# ethernet.net
KiCad netlist of a schematic drawn in Altium Designer
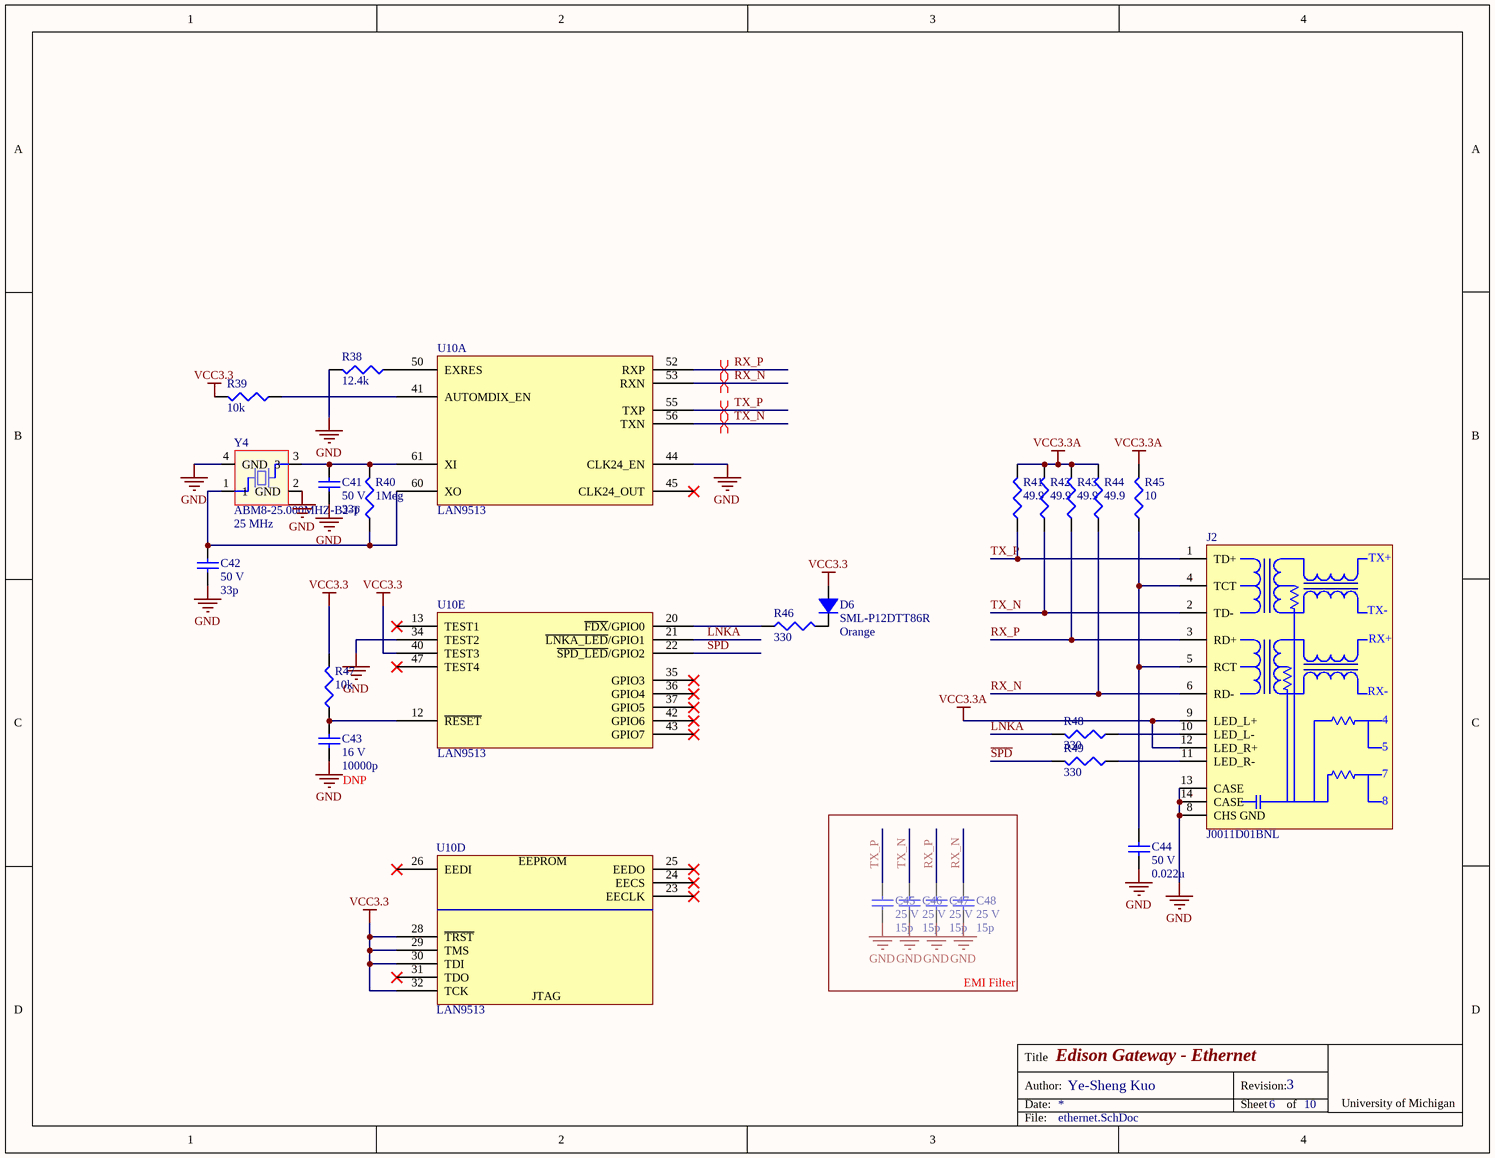
[diagram p0: ethernet.SchDoc]

(export (version "E")
  (design (tool "Eeschema 10.0.6"))
  (components
    (comp (ref "C41")
      (value "33p")
      (footprint "0402")
      (description "33pF ±5% 50V Ceramic Capacitor C0G, NP0 0402")
      (fields
        (field (name "VOLTAGE RATED") "50 V")
        (field (name "TOLERANCE") "5%")
        (field (name "MANUFACTURER PART NUMBER") "GRM1555C1H330JA01D")
      )
      (libsource (lib "capacitors") (part "GRM1555C1H330JA01D"))
    )
    (comp (ref "C42")
      (value "33p")
      (footprint "0402")
      (description "33pF ±5% 50V Ceramic Capacitor C0G, NP0 0402")
      (fields
        (field (name "VOLTAGE RATED") "50 V")
        (field (name "TOLERANCE") "5%")
        (field (name "MANUFACTURER PART NUMBER") "GRM1555C1H330JA01D")
      )
      (libsource (lib "capacitors") (part "GRM1555C1H330JA01D"))
    )
    (comp (ref "C43")
      (value "10000p")
      (footprint "0402")
      (description "10000pF ±10% 16V Ceramic Capacitor X7R 0402")
      (fields
        (field (name "TOLERANCE") "10%")
        (field (name "VOLTAGE RATED") "16 V")
        (field (name "MANUFACTURER PART NUMBER") "GRM155R71C103KA01D")
        (field (name "NOTE") "DNP")
      )
      (libsource (lib "capacitors") (part "GRM155R71C103KA01D"))
    )
    (comp (ref "C44")
      (value "0.022u")
      (footprint "0402")
      (description "0.022µF ±10% 50V Ceramic Capacitor X7R 0402")
      (fields
        (field (name "TOLERANCE") "10%")
        (field (name "VOLTAGE RATED") "50 V")
        (field (name "MANUFACTURER PART NUMBER") "GRM155R71H223KA12D")
      )
      (libsource (lib "capacitors") (part "GRM155R71H223KA12D"))
    )
    (comp (ref "C45")
      (value "15p")
      (footprint "0402")
      (description "15pF ±5% 25V Ceramic Capacitor C0G, NP0 0402")
      (fields
        (field (name "VOLTAGE RATED") "25 V")
        (field (name "TOLERANCE") "5%")
        (field (name "MANUFACTURER PART NUMBER") "GRM1555C1E150JA01D")
      )
      (libsource (lib "capacitors") (part "GRM1555C1E150JA01D"))
    )
    (comp (ref "C46")
      (value "15p")
      (footprint "0402")
      (description "15pF ±5% 25V Ceramic Capacitor C0G, NP0 0402")
      (fields
        (field (name "VOLTAGE RATED") "25 V")
        (field (name "TOLERANCE") "5%")
        (field (name "MANUFACTURER PART NUMBER") "GRM1555C1E150JA01D")
      )
      (libsource (lib "capacitors") (part "GRM1555C1E150JA01D"))
    )
    (comp (ref "C47")
      (value "15p")
      (footprint "0402")
      (description "15pF ±5% 25V Ceramic Capacitor C0G, NP0 0402")
      (fields
        (field (name "VOLTAGE RATED") "25 V")
        (field (name "TOLERANCE") "5%")
        (field (name "MANUFACTURER PART NUMBER") "GRM1555C1E150JA01D")
      )
      (libsource (lib "capacitors") (part "GRM1555C1E150JA01D"))
    )
    (comp (ref "C48")
      (value "15p")
      (footprint "0402")
      (description "15pF ±5% 25V Ceramic Capacitor C0G, NP0 0402")
      (fields
        (field (name "VOLTAGE RATED") "25 V")
        (field (name "TOLERANCE") "5%")
        (field (name "MANUFACTURER PART NUMBER") "GRM1555C1E150JA01D")
      )
      (libsource (lib "capacitors") (part "GRM1555C1E150JA01D"))
    )
    (comp (ref "D6")
      (value "SML-P12DTT86R")
      (footprint "0402 - LED")
      (description "Orange 605nm LED Indication - Discrete 2.1V 0402")
      (fields (field (name "MANUFACTURER") "Rohm Semiconductor") (field (name "ALTIUM_VALUE") "Orange"))
      (libsource (lib "LED") (part "SML-P12DTT86R"))
    )
    (comp (ref "J2")
      (value "J0011D01BNL")
      (footprint "J0011D01BNL")
      (description "1x1 Tab-Down RJ45")
      (libsource (lib "connectors") (part "J0011D01BNL"))
    )
    (comp (ref "R38")
      (value "12.4k")
      (footprint "0402")
      (description "RES SMD 12.4K OHM 1% 1/16W 0402")
      (fields (field (name "TOLERANCE") "1%") (field (name "POWER") "1/16 W"))
      (libsource (lib "resistors") (part "RC0402FR-0712K4L"))
    )
    (comp (ref "R39")
      (value "10k")
      (footprint "0402")
      (description "RES SMD 10K OHM 1% 1/16W 0402")
      (fields (field (name "TOLERANCE") "1%") (field (name "POWER") "1/16 W"))
      (libsource (lib "resistors") (part "CRCW040210K0FKED"))
    )
    (comp (ref "R40")
      (value "1Meg")
      (footprint "0402")
      (description "RES SMD 1M OHM 1% 1/16W 0402")
      (fields (field (name "TOLERANCE") "1%") (field (name "POWER") "1/16 W"))
      (libsource (lib "resistors") (part "CRCW04021M00FKED"))
    )
    (comp (ref "R41")
      (value "49.9")
      (footprint "0402")
      (description "RES SMD 49.9 OHM 1% 1/16W 0402")
      (fields (field (name "TOLERANCE") "1%") (field (name "POWER") "1/16 W"))
      (libsource (lib "resistors") (part "CRCW040249R9FKED"))
    )
    (comp (ref "R42")
      (value "49.9")
      (footprint "0402")
      (description "RES SMD 49.9 OHM 1% 1/16W 0402")
      (fields (field (name "TOLERANCE") "1%") (field (name "POWER") "1/16 W"))
      (libsource (lib "resistors") (part "CRCW040249R9FKED"))
    )
    (comp (ref "R43")
      (value "49.9")
      (footprint "0402")
      (description "RES SMD 49.9 OHM 1% 1/16W 0402")
      (fields (field (name "TOLERANCE") "1%") (field (name "POWER") "1/16 W"))
      (libsource (lib "resistors") (part "CRCW040249R9FKED"))
    )
    (comp (ref "R44")
      (value "49.9")
      (footprint "0402")
      (description "RES SMD 49.9 OHM 1% 1/16W 0402")
      (fields (field (name "TOLERANCE") "1%") (field (name "POWER") "1/16 W"))
      (libsource (lib "resistors") (part "CRCW040249R9FKED"))
    )
    (comp (ref "R45")
      (value "10")
      (footprint "0402")
      (description "RES SMD 10 OHM 1% 1/16W 0402")
      (fields (field (name "TOLERANCE") "1%") (field (name "POWER") "1/16 W"))
      (libsource (lib "resistors") (part "CRCW040210R0FKED"))
    )
    (comp (ref "R46")
      (value "330")
      (footprint "0402")
      (description "RES SMD 330 OHM 1% 1/16W 0402")
      (fields (field (name "TOLERANCE") "1%") (field (name "POWER") "1/16 W"))
      (libsource (lib "resistors") (part "CRCW0402330RFKED"))
    )
    (comp (ref "R47")
      (value "10k")
      (footprint "0402")
      (description "RES SMD 10K OHM 1% 1/16W 0402")
      (fields (field (name "TOLERANCE") "1%") (field (name "POWER") "1/16 W"))
      (libsource (lib "resistors") (part "CRCW040210K0FKED"))
    )
    (comp (ref "R48")
      (value "330")
      (footprint "0402")
      (description "RES SMD 330 OHM 1% 1/16W 0402")
      (fields (field (name "TOLERANCE") "1%") (field (name "POWER") "1/16 W"))
      (libsource (lib "resistors") (part "CRCW0402330RFKED"))
    )
    (comp (ref "R49")
      (value "330")
      (footprint "0402")
      (description "RES SMD 330 OHM 1% 1/16W 0402")
      (fields (field (name "TOLERANCE") "1%") (field (name "POWER") "1/16 W"))
      (libsource (lib "resistors") (part "CRCW0402330RFKED"))
    )
    (comp (ref "U10")
      (value "LAN9513")
      (footprint "QFN-64")
      (description "USB 2.0 Hub and 10/100  Ethernet Controller")
      (libsource (lib "ethernet controller") (part "LAN9513"))
    )
    (comp (ref "Y4")
      (value "ABM8-25.000MHZ-B2-T")
      (footprint "ABM8")
      (description "Crystal 25.0000MHz 20ppm 18pF 50 Ohm")
      (fields (field (name "FREQUENCY") "25 MHz"))
      (libsource (lib "crystal oscillators") (part "ABM8-25.000MHZ-B2-T"))
    )
  )
  (nets
    (net (code "1") (name "/RX_N") (class "Default")
      (node (ref "C48") (pin "1") (pintype "passive"))
      (node (ref "J2") (pin "6") (pinfunction "RD-_6") (pintype "passive"))
      (node (ref "R44") (pin "2") (pintype "passive"))
      (node (ref "U10") (pin "53") (pinfunction "RXN_53") (pintype "passive"))
    )
    (net (code "2") (name "/RX_P") (class "Default")
      (node (ref "C47") (pin "1") (pintype "passive"))
      (node (ref "J2") (pin "3") (pinfunction "RD+_3") (pintype "passive"))
      (node (ref "R43") (pin "2") (pintype "passive"))
      (node (ref "U10") (pin "52") (pinfunction "RXP_52") (pintype "passive"))
    )
    (net (code "3") (name "/TX_N") (class "Default")
      (node (ref "C46") (pin "1") (pintype "passive"))
      (node (ref "J2") (pin "2") (pinfunction "TD-_2") (pintype "passive"))
      (node (ref "R42") (pin "2") (pintype "passive"))
      (node (ref "U10") (pin "56") (pinfunction "TXN_56") (pintype "passive"))
    )
    (net (code "4") (name "/TX_P") (class "Default")
      (node (ref "C45") (pin "1") (pintype "passive"))
      (node (ref "J2") (pin "1") (pinfunction "TD+_1") (pintype "passive"))
      (node (ref "R41") (pin "2") (pintype "passive"))
      (node (ref "U10") (pin "55") (pinfunction "TXP_55") (pintype "passive"))
    )
    (net (code "5") (name "/~{LNKA}") (class "Default")
      (node (ref "R48") (pin "1") (pintype "passive"))
      (node (ref "U10") (pin "21") (pinfunction "~{LNKA_LED}/GPIO1_21") (pintype "passive"))
    )
    (net (code "6") (name "/~{SPD}") (class "Default")
      (node (ref "R49") (pin "1") (pintype "passive"))
      (node (ref "U10") (pin "22") (pinfunction "~{SPD_LED}/GPIO2_22") (pintype "passive"))
    )
    (net (code "7") (name "GND") (class "Default")
      (node (ref "C41") (pin "2") (pintype "passive"))
      (node (ref "C42") (pin "2") (pintype "passive"))
      (node (ref "C43") (pin "2") (pintype "passive"))
      (node (ref "C44") (pin "2") (pintype "passive"))
      (node (ref "C45") (pin "2") (pintype "passive"))
      (node (ref "C46") (pin "2") (pintype "passive"))
      (node (ref "C47") (pin "2") (pintype "passive"))
      (node (ref "C48") (pin "2") (pintype "passive"))
      (node (ref "J2") (pin "13") (pinfunction "CASE_13") (pintype "passive"))
      (node (ref "J2") (pin "14") (pinfunction "CASE_14") (pintype "passive"))
      (node (ref "J2") (pin "8") (pinfunction "CHS_GND_8") (pintype "passive"))
      (node (ref "R38") (pin "1") (pintype "passive"))
      (node (ref "U10") (pin "34") (pinfunction "TEST2_34") (pintype "passive"))
      (node (ref "U10") (pin "44") (pinfunction "CLK24_EN_44") (pintype "passive"))
      (node (ref "Y4") (pin "2") (pinfunction "GND_2") (pintype "passive"))
      (node (ref "Y4") (pin "4") (pinfunction "GND_4") (pintype "passive"))
    )
    (net (code "8") (name "Net-(D6-Pad2)") (class "Default")
      (node (ref "D6") (pin "2") (pintype "passive"))
      (node (ref "R46") (pin "1") (pintype "passive"))
    )
    (net (code "9") (name "Net-(J2-LED_L-)") (class "Default")
      (node (ref "J2") (pin "10") (pinfunction "LED_L-_10") (pintype "passive"))
      (node (ref "R48") (pin "2") (pintype "passive"))
    )
    (net (code "10") (name "Net-(J2-LED_R-)") (class "Default")
      (node (ref "J2") (pin "11") (pinfunction "LED_R-_11") (pintype "passive"))
      (node (ref "R49") (pin "2") (pintype "passive"))
    )
    (net (code "11") (name "Net-(J2-RCT)") (class "Default")
      (node (ref "C44") (pin "1") (pintype "passive"))
      (node (ref "J2") (pin "4") (pinfunction "TCT_4") (pintype "passive"))
      (node (ref "J2") (pin "5") (pinfunction "RCT_5") (pintype "passive"))
      (node (ref "R45") (pin "2") (pintype "passive"))
    )
    (net (code "12") (name "Net-(U10A-AUTOMDIX_EN)") (class "Default")
      (node (ref "R39") (pin "2") (pintype "passive"))
      (node (ref "U10") (pin "41") (pinfunction "AUTOMDIX_EN_41") (pintype "passive"))
    )
    (net (code "13") (name "Net-(U10A-EXRES)") (class "Default")
      (node (ref "R38") (pin "2") (pintype "passive"))
      (node (ref "U10") (pin "50") (pinfunction "EXRES_50") (pintype "passive"))
    )
    (net (code "14") (name "Net-(U10A-XI)") (class "Default")
      (node (ref "C41") (pin "1") (pintype "passive"))
      (node (ref "R40") (pin "1") (pintype "passive"))
      (node (ref "U10") (pin "61") (pinfunction "XI_61") (pintype "passive"))
      (node (ref "Y4") (pin "3") (pinfunction "3_3") (pintype "passive"))
    )
    (net (code "15") (name "Net-(U10A-XO)") (class "Default")
      (node (ref "C42") (pin "1") (pintype "passive"))
      (node (ref "R40") (pin "2") (pintype "passive"))
      (node (ref "U10") (pin "60") (pinfunction "XO_60") (pintype "passive"))
      (node (ref "Y4") (pin "1") (pinfunction "1_1") (pintype "passive"))
    )
    (net (code "16") (name "Net-(U10E-~{FDX}{slash}GPIO0)") (class "Default")
      (node (ref "R46") (pin "2") (pintype "passive"))
      (node (ref "U10") (pin "20") (pinfunction "~{FDX}/GPIO0_20") (pintype "passive"))
    )
    (net (code "17") (name "Net-(U10E-~{RESET})") (class "Default")
      (node (ref "C43") (pin "1") (pintype "passive"))
      (node (ref "R47") (pin "2") (pintype "passive"))
      (node (ref "U10") (pin "12") (pinfunction "~{RESET}_12") (pintype "passive"))
    )
    (net (code "18") (name "VCC3.3") (class "Default")
      (node (ref "D6") (pin "1") (pintype "passive"))
      (node (ref "R39") (pin "1") (pintype "passive"))
      (node (ref "R47") (pin "1") (pintype "passive"))
      (node (ref "U10") (pin "28") (pinfunction "~{TRST}_28") (pintype "passive"))
      (node (ref "U10") (pin "29") (pinfunction "TMS_29") (pintype "passive"))
      (node (ref "U10") (pin "30") (pinfunction "TDI_30") (pintype "passive"))
      (node (ref "U10") (pin "32") (pinfunction "TCK_32") (pintype "passive"))
      (node (ref "U10") (pin "40") (pinfunction "TEST3_40") (pintype "passive"))
    )
    (net (code "19") (name "VCC3.3A") (class "Default")
      (node (ref "J2") (pin "12") (pinfunction "LED_R+_12") (pintype "passive"))
      (node (ref "J2") (pin "9") (pinfunction "LED_L+_9") (pintype "passive"))
      (node (ref "R41") (pin "1") (pintype "passive"))
      (node (ref "R42") (pin "1") (pintype "passive"))
      (node (ref "R43") (pin "1") (pintype "passive"))
      (node (ref "R44") (pin "1") (pintype "passive"))
      (node (ref "R45") (pin "1") (pintype "passive"))
    )
    (net (code "20") (name "unconnected-(U10A-CLK24_OUT-Pad45)") (class "Default")
      (node (ref "U10") (pin "45") (pinfunction "CLK24_OUT_45") (pintype "passive+no_connect"))
    )
    (net (code "21") (name "unconnected-(U10D-EECLK-Pad23)") (class "Default")
      (node (ref "U10") (pin "23") (pinfunction "EECLK_23") (pintype "passive+no_connect"))
    )
    (net (code "22") (name "unconnected-(U10D-EECS-Pad24)") (class "Default")
      (node (ref "U10") (pin "24") (pinfunction "EECS_24") (pintype "passive+no_connect"))
    )
    (net (code "23") (name "unconnected-(U10D-EEDI-Pad26)") (class "Default")
      (node (ref "U10") (pin "26") (pinfunction "EEDI_26") (pintype "passive+no_connect"))
    )
    (net (code "24") (name "unconnected-(U10D-EEDO-Pad25)") (class "Default")
      (node (ref "U10") (pin "25") (pinfunction "EEDO_25") (pintype "passive+no_connect"))
    )
    (net (code "25") (name "unconnected-(U10D-TDO-Pad31)") (class "Default")
      (node (ref "U10") (pin "31") (pinfunction "TDO_31") (pintype "passive+no_connect"))
    )
    (net (code "26") (name "unconnected-(U10E-GPIO3-Pad35)") (class "Default")
      (node (ref "U10") (pin "35") (pinfunction "GPIO3_35") (pintype "passive+no_connect"))
    )
    (net (code "27") (name "unconnected-(U10E-GPIO4-Pad36)") (class "Default")
      (node (ref "U10") (pin "36") (pinfunction "GPIO4_36") (pintype "passive+no_connect"))
    )
    (net (code "28") (name "unconnected-(U10E-GPIO5-Pad37)") (class "Default")
      (node (ref "U10") (pin "37") (pinfunction "GPIO5_37") (pintype "passive+no_connect"))
    )
    (net (code "29") (name "unconnected-(U10E-GPIO6-Pad42)") (class "Default")
      (node (ref "U10") (pin "42") (pinfunction "GPIO6_42") (pintype "passive+no_connect"))
    )
    (net (code "30") (name "unconnected-(U10E-GPIO7-Pad43)") (class "Default")
      (node (ref "U10") (pin "43") (pinfunction "GPIO7_43") (pintype "passive+no_connect"))
    )
    (net (code "31") (name "unconnected-(U10E-TEST1-Pad13)") (class "Default")
      (node (ref "U10") (pin "13") (pinfunction "TEST1_13") (pintype "passive+no_connect"))
    )
    (net (code "32") (name "unconnected-(U10E-TEST4-Pad47)") (class "Default")
      (node (ref "U10") (pin "47") (pinfunction "TEST4_47") (pintype "passive+no_connect"))
    )
  )
)
